# Resolver.net
KiCad netlist of a schematic drawn in Altium Designer
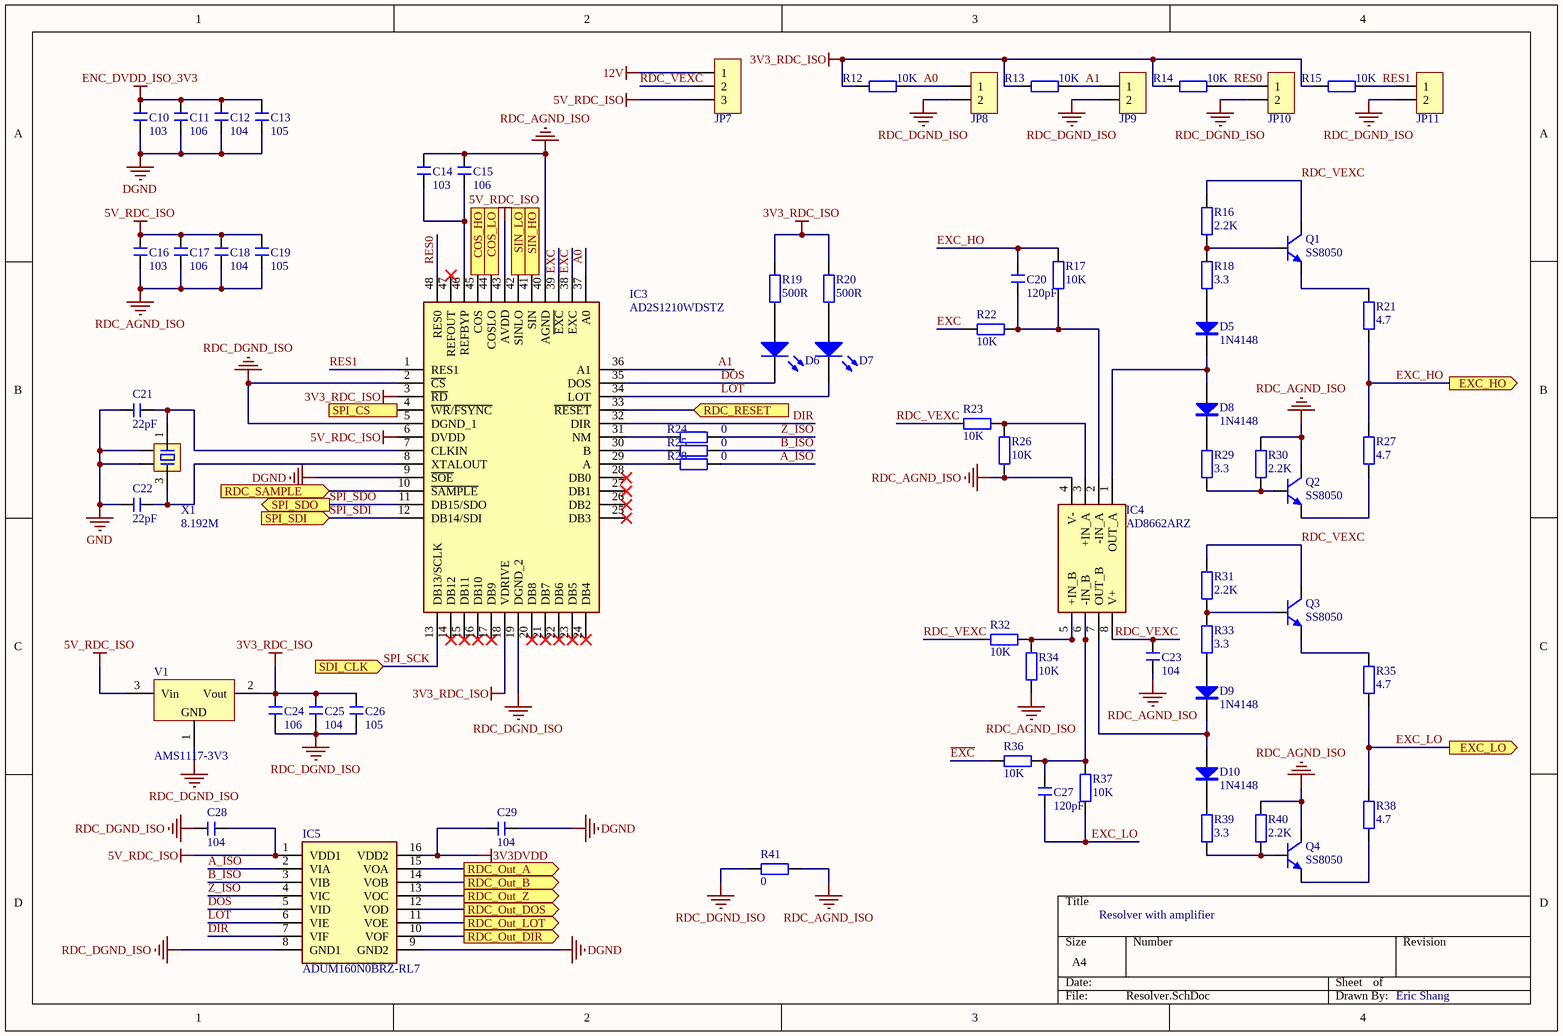
[diagram p0: Resolver.SchDoc]

(export (version "E")
  (design (tool "Eeschema 10.0.6"))
  (components
    (comp (ref "C10")
      (value "103")
      (footprint "C 0603_L")
      (description "贴片电容")
      (libsource (lib "0.1 - 电阻-电容-电感") (part "C"))
    )
    (comp (ref "C11")
      (value "106")
      (footprint "C 0603_L")
      (description "贴片电容")
      (libsource (lib "0.1 - 电阻-电容-电感") (part "C"))
    )
    (comp (ref "C12")
      (value "104")
      (footprint "C 0603_L")
      (description "贴片电容")
      (libsource (lib "0.1 - 电阻-电容-电感") (part "C"))
    )
    (comp (ref "C13")
      (value "105")
      (footprint "C 0603_L")
      (description "贴片电容")
      (libsource (lib "0.1 - 电阻-电容-电感") (part "C"))
    )
    (comp (ref "C14")
      (value "103")
      (footprint "C 0603_L")
      (description "贴片电容")
      (libsource (lib "0.1 - 电阻-电容-电感") (part "C"))
    )
    (comp (ref "C15")
      (value "106")
      (footprint "C 0603_L")
      (description "贴片电容")
      (libsource (lib "0.1 - 电阻-电容-电感") (part "C"))
    )
    (comp (ref "C16")
      (value "103")
      (footprint "C 0603_L")
      (description "贴片电容")
      (libsource (lib "0.1 - 电阻-电容-电感") (part "C"))
    )
    (comp (ref "C17")
      (value "106")
      (footprint "C 0603_L")
      (description "贴片电容")
      (libsource (lib "0.1 - 电阻-电容-电感") (part "C"))
    )
    (comp (ref "C18")
      (value "104")
      (footprint "C 0603_L")
      (description "贴片电容")
      (libsource (lib "0.1 - 电阻-电容-电感") (part "C"))
    )
    (comp (ref "C19")
      (value "105")
      (footprint "C 0603_L")
      (description "贴片电容")
      (libsource (lib "0.1 - 电阻-电容-电感") (part "C"))
    )
    (comp (ref "C20")
      (value "120pF")
      (footprint "C 0603_L")
      (description "贴片电容")
      (libsource (lib "0.1 - 电阻-电容-电感") (part "C"))
    )
    (comp (ref "C21")
      (value "22pF")
      (footprint "C 0603_L")
      (description "贴片电容")
      (libsource (lib "0.1 - 电阻-电容-电感") (part "C"))
    )
    (comp (ref "C22")
      (value "22pF")
      (footprint "C 0603_L")
      (description "贴片电容")
      (libsource (lib "0.1 - 电阻-电容-电感") (part "C"))
    )
    (comp (ref "C23")
      (value "104")
      (footprint "C 0603_L")
      (description "贴片电容")
      (libsource (lib "0.1 - 电阻-电容-电感") (part "C"))
    )
    (comp (ref "C24")
      (value "106")
      (footprint "C 0603_L")
      (description "贴片电容")
      (libsource (lib "0.1 - 电阻-电容-电感") (part "C"))
    )
    (comp (ref "C25")
      (value "104")
      (footprint "C 0603_L")
      (description "贴片电容")
      (libsource (lib "0.1 - 电阻-电容-电感") (part "C"))
    )
    (comp (ref "C26")
      (value "105")
      (footprint "C 0603_L")
      (description "贴片电容")
      (libsource (lib "0.1 - 电阻-电容-电感") (part "C"))
    )
    (comp (ref "C27")
      (value "120pF")
      (footprint "C 0603_L")
      (description "贴片电容")
      (libsource (lib "0.1 - 电阻-电容-电感") (part "C"))
    )
    (comp (ref "C28")
      (value "104")
      (footprint "C 0603_L")
      (description "贴片电容")
      (libsource (lib "0.1 - 电阻-电容-电感") (part "C"))
    )
    (comp (ref "C29")
      (value "104")
      (footprint "C 0603_L")
      (description "贴片电容")
      (libsource (lib "0.1 - 电阻-电容-电感") (part "C"))
    )
    (comp (ref "D5")
      (value "1N4148")
      (footprint "MINI_MELF (LL34)")
      (description "开关二极管")
      (libsource (lib "0.2 -  二极管-整流桥") (part "1N4148"))
    )
    (comp (ref "D6")
      (value "LED")
      (footprint "LED 0603W")
      (description "发光二极管")
      (libsource (lib "0.3 - LED发光二极管") (part "LED"))
    )
    (comp (ref "D7")
      (value "LED")
      (footprint "LED 0603W")
      (description "发光二极管")
      (libsource (lib "0.3 - LED发光二极管") (part "LED"))
    )
    (comp (ref "D8")
      (value "1N4148")
      (footprint "MINI_MELF (LL34)")
      (description "开关二极管")
      (libsource (lib "0.2 -  二极管-整流桥") (part "1N4148"))
    )
    (comp (ref "D9")
      (value "1N4148")
      (footprint "MINI_MELF (LL34)")
      (description "开关二极管")
      (libsource (lib "0.2 -  二极管-整流桥") (part "1N4148"))
    )
    (comp (ref "D10")
      (value "1N4148")
      (footprint "MINI_MELF (LL34)")
      (description "开关二极管")
      (libsource (lib "0.2 -  二极管-整流桥") (part "1N4148"))
    )
    (comp (ref "IC3")
      (value "AD2S1210WDSTZ")
      (footprint "SkylakeADPcbLib:QFP50P900X900X160-48N")
      (description "Integrated Circuit")
      (fields (field (name "MOUSER PART NUMBER") "584-AD2S1210WDSTZ"))
      (libsource (lib "*") (part "AD2S1210WDSTZ"))
    )
    (comp (ref "IC4")
      (value "AD8662ARZ")
      (footprint "SkylakeADPcbLib:SOIC127P600X175-8N")
      (description "Integrated Circuit")
      (fields (field (name "MOUSER PART NUMBER") "584-AD8662ARZ"))
      (libsource (lib "*") (part "AD8662ARZ"))
    )
    (comp (ref "IC5")
      (value "ADUM160N0BRZ-RL7")
      (footprint "SkylakeADPcbLib:SOIC127P600X175-16N")
      (description "Integrated Circuit")
      (fields (field (name "MOUSER PART NUMBER") "584-ADUM160N0BRZ-RL7"))
      (libsource (lib "*") (part "ADUM160N0BRZ-RL7"))
    )
    (comp (ref "JP7")
      (value "HDR-1X3")
      (footprint "HDR2.54-LI-3P")
      (description "3P接插件")
      (fields (field (name "版权归属") "封装库来自淘宝 ID：黄晶宝石"))
      (libsource (lib "5.3 - 接插件-脚距2.54 (100mil) ") (part "Header 3"))
    )
    (comp (ref "JP8")
      (value "HDR-1X2")
      (footprint "HDR2.54-LI-2P")
      (description "2P接插件")
      (fields (field (name "版权归属") "封装库来自淘宝 ID：黄晶宝石"))
      (libsource (lib "5.3 - 接插件-脚距2.54 (100mil) ") (part "Header 2"))
    )
    (comp (ref "JP9")
      (value "HDR-1X2")
      (footprint "HDR2.54-LI-2P")
      (description "2P接插件")
      (fields (field (name "版权归属") "封装库来自淘宝 ID：黄晶宝石"))
      (libsource (lib "5.3 - 接插件-脚距2.54 (100mil) ") (part "Header 2"))
    )
    (comp (ref "JP10")
      (value "HDR-1X2")
      (footprint "HDR2.54-LI-2P")
      (description "2P接插件")
      (fields (field (name "版权归属") "封装库来自淘宝 ID：黄晶宝石"))
      (libsource (lib "5.3 - 接插件-脚距2.54 (100mil) ") (part "Header 2"))
    )
    (comp (ref "JP11")
      (value "HDR-1X2")
      (footprint "HDR2.54-LI-2P")
      (description "2P接插件")
      (fields (field (name "版权归属") "封装库来自淘宝 ID：黄晶宝石"))
      (libsource (lib "5.3 - 接插件-脚距2.54 (100mil) ") (part "Header 2"))
    )
    (comp (ref "Q1")
      (value "SS8050")
      (footprint "SOT23-3N")
      (description "高频放大-NPN型")
      (fields (field (name "版权归属") "封装库来自淘宝 ID：黄晶宝石"))
      (libsource (lib "0.4 - 三极管") (part "8050-SMD"))
    )
    (comp (ref "Q2")
      (value "SS8050")
      (footprint "SOT23-3N")
      (description "高频放大-NPN型")
      (fields (field (name "版权归属") "封装库来自淘宝 ID：黄晶宝石"))
      (libsource (lib "0.4 - 三极管") (part "8050-SMD"))
    )
    (comp (ref "Q3")
      (value "SS8050")
      (footprint "SOT23-3N")
      (description "高频放大-NPN型")
      (fields (field (name "版权归属") "封装库来自淘宝 ID：黄晶宝石"))
      (libsource (lib "0.4 - 三极管") (part "8050-SMD"))
    )
    (comp (ref "Q4")
      (value "SS8050")
      (footprint "SOT23-3N")
      (description "高频放大-NPN型")
      (fields (field (name "版权归属") "封装库来自淘宝 ID：黄晶宝石"))
      (libsource (lib "0.4 - 三极管") (part "8050-SMD"))
    )
    (comp (ref "R12")
      (value "10K")
      (footprint "R 0603_L")
      (description "贴片电阻")
      (fields (field (name "版权归属") "来自淘宝 ID：黄晶宝石"))
      (libsource (lib "0.1 - 电阻-电容-电感") (part "R"))
    )
    (comp (ref "R13")
      (value "10K")
      (footprint "R 0603_L")
      (description "贴片电阻")
      (fields (field (name "版权归属") "来自淘宝 ID：黄晶宝石"))
      (libsource (lib "0.1 - 电阻-电容-电感") (part "R"))
    )
    (comp (ref "R14")
      (value "10K")
      (footprint "R 0603_L")
      (description "贴片电阻")
      (fields (field (name "版权归属") "来自淘宝 ID：黄晶宝石"))
      (libsource (lib "0.1 - 电阻-电容-电感") (part "R"))
    )
    (comp (ref "R15")
      (value "10K")
      (footprint "R 0603_L")
      (description "贴片电阻")
      (fields (field (name "版权归属") "来自淘宝 ID：黄晶宝石"))
      (libsource (lib "0.1 - 电阻-电容-电感") (part "R"))
    )
    (comp (ref "R16")
      (value "2.2K")
      (footprint "R 0603_L")
      (description "贴片电阻")
      (fields (field (name "版权归属") "来自淘宝 ID：黄晶宝石"))
      (libsource (lib "0.1 - 电阻-电容-电感") (part "R"))
    )
    (comp (ref "R17")
      (value "10K")
      (footprint "R 0603_L")
      (description "贴片电阻")
      (fields (field (name "版权归属") "来自淘宝 ID：黄晶宝石"))
      (libsource (lib "0.1 - 电阻-电容-电感") (part "R"))
    )
    (comp (ref "R18")
      (value "3.3")
      (footprint "R 0603_L")
      (description "贴片电阻")
      (fields (field (name "版权归属") "来自淘宝 ID：黄晶宝石"))
      (libsource (lib "0.1 - 电阻-电容-电感") (part "R"))
    )
    (comp (ref "R19")
      (value "500R")
      (footprint "R 0603_L")
      (description "贴片电阻")
      (fields (field (name "版权归属") "来自淘宝 ID：黄晶宝石"))
      (libsource (lib "0.1 - 电阻-电容-电感") (part "R"))
    )
    (comp (ref "R20")
      (value "500R")
      (footprint "R 0603_L")
      (description "贴片电阻")
      (fields (field (name "版权归属") "来自淘宝 ID：黄晶宝石"))
      (libsource (lib "0.1 - 电阻-电容-电感") (part "R"))
    )
    (comp (ref "R21")
      (value "4.7")
      (footprint "R 1206_L")
      (description "贴片电阻")
      (fields (field (name "版权归属") "来自淘宝 ID：黄晶宝石"))
      (libsource (lib "0.1 - 电阻-电容-电感") (part "R"))
    )
    (comp (ref "R22")
      (value "10K")
      (footprint "R 0603_L")
      (description "贴片电阻")
      (fields (field (name "版权归属") "来自淘宝 ID：黄晶宝石"))
      (libsource (lib "0.1 - 电阻-电容-电感") (part "R"))
    )
    (comp (ref "R23")
      (value "10K")
      (footprint "R 0603_L")
      (description "贴片电阻")
      (fields (field (name "版权归属") "来自淘宝 ID：黄晶宝石"))
      (libsource (lib "0.1 - 电阻-电容-电感") (part "R"))
    )
    (comp (ref "R24")
      (value "0")
      (footprint "R 0603_L")
      (description "贴片电阻")
      (fields (field (name "版权归属") "来自淘宝 ID：黄晶宝石"))
      (libsource (lib "0.1 - 电阻-电容-电感") (part "R"))
    )
    (comp (ref "R25")
      (value "0")
      (footprint "R 0603_L")
      (description "贴片电阻")
      (fields (field (name "版权归属") "来自淘宝 ID：黄晶宝石"))
      (libsource (lib "0.1 - 电阻-电容-电感") (part "R"))
    )
    (comp (ref "R26")
      (value "10K")
      (footprint "R 0603_L")
      (description "贴片电阻")
      (fields (field (name "版权归属") "来自淘宝 ID：黄晶宝石"))
      (libsource (lib "0.1 - 电阻-电容-电感") (part "R"))
    )
    (comp (ref "R27")
      (value "4.7")
      (footprint "R 1206_L")
      (description "贴片电阻")
      (fields (field (name "版权归属") "来自淘宝 ID：黄晶宝石"))
      (libsource (lib "0.1 - 电阻-电容-电感") (part "R"))
    )
    (comp (ref "R28")
      (value "0")
      (footprint "R 0603_L")
      (description "贴片电阻")
      (fields (field (name "版权归属") "来自淘宝 ID：黄晶宝石"))
      (libsource (lib "0.1 - 电阻-电容-电感") (part "R"))
    )
    (comp (ref "R29")
      (value "3.3")
      (footprint "R 0603_L")
      (description "贴片电阻")
      (fields (field (name "版权归属") "来自淘宝 ID：黄晶宝石"))
      (libsource (lib "0.1 - 电阻-电容-电感") (part "R"))
    )
    (comp (ref "R30")
      (value "2.2K")
      (footprint "R 0603_L")
      (description "贴片电阻")
      (fields (field (name "版权归属") "来自淘宝 ID：黄晶宝石"))
      (libsource (lib "0.1 - 电阻-电容-电感") (part "R"))
    )
    (comp (ref "R31")
      (value "2.2K")
      (footprint "R 0603_L")
      (description "贴片电阻")
      (fields (field (name "版权归属") "来自淘宝 ID：黄晶宝石"))
      (libsource (lib "0.1 - 电阻-电容-电感") (part "R"))
    )
    (comp (ref "R32")
      (value "10K")
      (footprint "R 0603_L")
      (description "贴片电阻")
      (fields (field (name "版权归属") "来自淘宝 ID：黄晶宝石"))
      (libsource (lib "0.1 - 电阻-电容-电感") (part "R"))
    )
    (comp (ref "R33")
      (value "3.3")
      (footprint "R 0603_L")
      (description "贴片电阻")
      (fields (field (name "版权归属") "来自淘宝 ID：黄晶宝石"))
      (libsource (lib "0.1 - 电阻-电容-电感") (part "R"))
    )
    (comp (ref "R34")
      (value "10K")
      (footprint "R 0603_L")
      (description "贴片电阻")
      (fields (field (name "版权归属") "来自淘宝 ID：黄晶宝石"))
      (libsource (lib "0.1 - 电阻-电容-电感") (part "R"))
    )
    (comp (ref "R35")
      (value "4.7")
      (footprint "R 1206_L")
      (description "贴片电阻")
      (fields (field (name "版权归属") "来自淘宝 ID：黄晶宝石"))
      (libsource (lib "0.1 - 电阻-电容-电感") (part "R"))
    )
    (comp (ref "R36")
      (value "10K")
      (footprint "R 0603_L")
      (description "贴片电阻")
      (fields (field (name "版权归属") "来自淘宝 ID：黄晶宝石"))
      (libsource (lib "0.1 - 电阻-电容-电感") (part "R"))
    )
    (comp (ref "R37")
      (value "10K")
      (footprint "R 0603_L")
      (description "贴片电阻")
      (fields (field (name "版权归属") "来自淘宝 ID：黄晶宝石"))
      (libsource (lib "0.1 - 电阻-电容-电感") (part "R"))
    )
    (comp (ref "R38")
      (value "4.7")
      (footprint "R 1206_L")
      (description "贴片电阻")
      (fields (field (name "版权归属") "来自淘宝 ID：黄晶宝石"))
      (libsource (lib "0.1 - 电阻-电容-电感") (part "R"))
    )
    (comp (ref "R39")
      (value "3.3")
      (footprint "R 0603_L")
      (description "贴片电阻")
      (fields (field (name "版权归属") "来自淘宝 ID：黄晶宝石"))
      (libsource (lib "0.1 - 电阻-电容-电感") (part "R"))
    )
    (comp (ref "R40")
      (value "2.2K")
      (footprint "R 0603_L")
      (description "贴片电阻")
      (fields (field (name "版权归属") "来自淘宝 ID：黄晶宝石"))
      (libsource (lib "0.1 - 电阻-电容-电感") (part "R"))
    )
    (comp (ref "R41")
      (value "0")
      (footprint "R 1206_L")
      (description "贴片电阻")
      (fields (field (name "版权归属") "来自淘宝 ID：黄晶宝石"))
      (libsource (lib "0.1 - 电阻-电容-电感") (part "R"))
    )
    (comp (ref "V1")
      (value "AMS1117-3V3")
      (footprint "SOT223_L")
      (description "三端稳压芯片")
      (libsource (lib "1.1 - 电源类芯片") (part "AMS1117"))
    )
    (comp (ref "X1")
      (value "8.192M")
      (footprint "OSC 1612-4P")
      (description "4脚无源晶振")
      (fields (field (name "版权归属") "封装库来自淘宝卖家 ID：黄晶宝石"))
      (libsource (lib "2.0 - 保险丝-晶振-光耦") (part "XTAL-4P"))
    )
  )
  (nets
    (net (code "1") (name "/A0") (class "Default")
      (node (ref "IC3") (pin "37") (pinfunction "A0_37") (pintype "passive"))
      (node (ref "JP8") (pin "1") (pinfunction "1_1") (pintype "passive"))
      (node (ref "R12") (pin "2") (pinfunction "2_2") (pintype "passive"))
    )
    (net (code "2") (name "/A1") (class "Default")
      (node (ref "IC3") (pin "36") (pinfunction "A1_36") (pintype "passive"))
      (node (ref "JP9") (pin "1") (pinfunction "1_1") (pintype "passive"))
      (node (ref "R13") (pin "2") (pinfunction "2_2") (pintype "passive"))
    )
    (net (code "3") (name "/A_ISO") (class "Default")
      (node (ref "IC5") (pin "2") (pinfunction "VIA_2") (pintype "passive"))
      (node (ref "R28") (pin "2") (pinfunction "2_2") (pintype "passive"))
    )
    (net (code "4") (name "/B_ISO") (class "Default")
      (node (ref "IC5") (pin "3") (pinfunction "VIB_3") (pintype "passive"))
      (node (ref "R25") (pin "2") (pinfunction "2_2") (pintype "passive"))
    )
    (net (code "5") (name "/COS_HO") (class "Default")
      (node (ref "IC3") (pin "45") (pinfunction "COS_45") (pintype "passive"))
    )
    (net (code "6") (name "/COS_LO") (class "Default")
      (node (ref "IC3") (pin "44") (pinfunction "COSLO_44") (pintype "passive"))
    )
    (net (code "7") (name "/DIR") (class "Default")
      (node (ref "IC3") (pin "32") (pinfunction "DIR_32") (pintype "passive"))
      (node (ref "IC5") (pin "7") (pinfunction "VIF_7") (pintype "passive"))
    )
    (net (code "8") (name "/DOS") (class "Default")
      (node (ref "D6") (pin "2") (pinfunction "K_2") (pintype "passive"))
      (node (ref "IC3") (pin "35") (pinfunction "DOS_35") (pintype "passive"))
      (node (ref "IC5") (pin "5") (pinfunction "VID_5") (pintype "passive"))
    )
    (net (code "9") (name "/EXC") (class "Default")
      (node (ref "IC3") (pin "38") (pinfunction "EXC_38") (pintype "passive"))
      (node (ref "R22") (pin "1") (pinfunction "1_1") (pintype "passive"))
    )
    (net (code "10") (name "/EXC_HO") (class "Default")
      (node (ref "C20") (pin "2") (pinfunction "2_2") (pintype "passive"))
      (node (ref "R17") (pin "2") (pinfunction "2_2") (pintype "passive"))
      (node (ref "R21") (pin "1") (pinfunction "1_1") (pintype "passive"))
      (node (ref "R27") (pin "2") (pinfunction "2_2") (pintype "passive"))
    )
    (net (code "11") (name "/EXC_LO") (class "Default")
      (node (ref "C27") (pin "1") (pinfunction "1_1") (pintype "passive"))
      (node (ref "R35") (pin "1") (pinfunction "1_1") (pintype "passive"))
      (node (ref "R37") (pin "1") (pinfunction "1_1") (pintype "passive"))
      (node (ref "R38") (pin "2") (pinfunction "2_2") (pintype "passive"))
    )
    (net (code "12") (name "/LOT") (class "Default")
      (node (ref "D7") (pin "2") (pinfunction "K_2") (pintype "passive"))
      (node (ref "IC3") (pin "34") (pinfunction "LOT_34") (pintype "passive"))
      (node (ref "IC5") (pin "6") (pinfunction "VIE_6") (pintype "passive"))
    )
    (net (code "13") (name "/RDC_Out_A") (class "Default")
      (node (ref "IC5") (pin "15") (pinfunction "VOA_15") (pintype "passive"))
    )
    (net (code "14") (name "/RDC_Out_B") (class "Default")
      (node (ref "IC5") (pin "14") (pinfunction "VOB_14") (pintype "passive"))
    )
    (net (code "15") (name "/RDC_Out_DIR") (class "Default")
      (node (ref "IC5") (pin "10") (pinfunction "VOF_10") (pintype "passive"))
    )
    (net (code "16") (name "/RDC_Out_DOS") (class "Default")
      (node (ref "IC5") (pin "12") (pinfunction "VOD_12") (pintype "passive"))
    )
    (net (code "17") (name "/RDC_Out_LOT") (class "Default")
      (node (ref "IC5") (pin "11") (pinfunction "VOE_11") (pintype "passive"))
    )
    (net (code "18") (name "/RDC_Out_Z") (class "Default")
      (node (ref "IC5") (pin "13") (pinfunction "VOC_13") (pintype "passive"))
    )
    (net (code "19") (name "/RDC_RESET") (class "Default")
      (node (ref "IC3") (pin "33") (pinfunction "~{RESET}_33") (pintype "passive"))
    )
    (net (code "20") (name "/RDC_SAMPLE") (class "Default")
      (node (ref "IC3") (pin "10") (pinfunction "~{SAMPLE}_10") (pintype "passive"))
    )
    (net (code "21") (name "/RDC_VEXC") (class "Default")
      (node (ref "C23") (pin "2") (pinfunction "2_2") (pintype "passive"))
      (node (ref "IC4") (pin "8") (pinfunction "V+_8") (pintype "passive"))
      (node (ref "JP7") (pin "2") (pinfunction "2_2") (pintype "passive"))
      (node (ref "Q1") (pin "3") (pinfunction "C_3") (pintype "passive"))
      (node (ref "Q3") (pin "3") (pinfunction "C_3") (pintype "passive"))
      (node (ref "R16") (pin "2") (pinfunction "2_2") (pintype "passive"))
      (node (ref "R23") (pin "1") (pinfunction "1_1") (pintype "passive"))
      (node (ref "R31") (pin "2") (pinfunction "2_2") (pintype "passive"))
      (node (ref "R32") (pin "1") (pinfunction "1_1") (pintype "passive"))
    )
    (net (code "22") (name "/RES0") (class "Default")
      (node (ref "IC3") (pin "48") (pinfunction "RES0_48") (pintype "passive"))
      (node (ref "JP10") (pin "1") (pinfunction "1_1") (pintype "passive"))
      (node (ref "R14") (pin "2") (pinfunction "2_2") (pintype "passive"))
    )
    (net (code "23") (name "/RES1") (class "Default")
      (node (ref "IC3") (pin "1") (pinfunction "RES1_1") (pintype "passive"))
      (node (ref "JP11") (pin "1") (pinfunction "1_1") (pintype "passive"))
      (node (ref "R15") (pin "2") (pinfunction "2_2") (pintype "passive"))
    )
    (net (code "24") (name "/SIN_HO") (class "Default")
      (node (ref "IC3") (pin "41") (pinfunction "SIN_41") (pintype "passive"))
    )
    (net (code "25") (name "/SIN_LO") (class "Default")
      (node (ref "IC3") (pin "42") (pinfunction "SINLO_42") (pintype "passive"))
    )
    (net (code "26") (name "/SPI_CS") (class "Default")
      (node (ref "IC3") (pin "4") (pinfunction "~{WR}/~{FSYNC}_4") (pintype "passive"))
    )
    (net (code "27") (name "/SPI_SCK") (class "Default")
      (node (ref "IC3") (pin "13") (pinfunction "DB13/SCLK_13") (pintype "passive"))
    )
    (net (code "28") (name "/SPI_SDI") (class "Default")
      (node (ref "IC3") (pin "12") (pinfunction "DB14/SDI_12") (pintype "passive"))
    )
    (net (code "29") (name "/SPI_SDO") (class "Default")
      (node (ref "IC3") (pin "11") (pinfunction "DB15/SDO_11") (pintype "passive"))
    )
    (net (code "30") (name "/Z_ISO") (class "Default")
      (node (ref "IC5") (pin "4") (pinfunction "VIC_4") (pintype "passive"))
      (node (ref "R24") (pin "2") (pinfunction "2_2") (pintype "passive"))
    )
    (net (code "31") (name "/~{EXC}") (class "Default")
      (node (ref "IC3") (pin "39") (pinfunction "~{EXC}_39") (pintype "passive"))
      (node (ref "R36") (pin "1") (pinfunction "1_1") (pintype "passive"))
    )
    (net (code "32") (name "3V3DVDD") (class "Default")
      (node (ref "C29") (pin "1") (pinfunction "1_1") (pintype "passive"))
      (node (ref "IC5") (pin "16") (pinfunction "VDD2_16") (pintype "passive"))
    )
    (net (code "33") (name "3V3_RDC_ISO") (class "Default")
      (node (ref "C24") (pin "2") (pinfunction "2_2") (pintype "passive"))
      (node (ref "C25") (pin "2") (pinfunction "2_2") (pintype "passive"))
      (node (ref "C26") (pin "2") (pinfunction "2_2") (pintype "passive"))
      (node (ref "IC3") (pin "18") (pinfunction "VDRIVE_18") (pintype "passive"))
      (node (ref "IC3") (pin "3") (pinfunction "~{RD}_3") (pintype "passive"))
      (node (ref "R12") (pin "1") (pinfunction "1_1") (pintype "passive"))
      (node (ref "R13") (pin "1") (pinfunction "1_1") (pintype "passive"))
      (node (ref "R14") (pin "1") (pinfunction "1_1") (pintype "passive"))
      (node (ref "R15") (pin "1") (pinfunction "1_1") (pintype "passive"))
      (node (ref "R19") (pin "2") (pinfunction "2_2") (pintype "passive"))
      (node (ref "R20") (pin "2") (pinfunction "2_2") (pintype "passive"))
      (node (ref "V1") (pin "2") (pinfunction "Vout_2") (pintype "passive"))
    )
    (net (code "34") (name "5V_RDC_ISO") (class "Default")
      (node (ref "C16") (pin "2") (pinfunction "2_2") (pintype "passive"))
      (node (ref "C17") (pin "2") (pinfunction "2_2") (pintype "passive"))
      (node (ref "C18") (pin "2") (pinfunction "2_2") (pintype "passive"))
      (node (ref "C19") (pin "2") (pinfunction "2_2") (pintype "passive"))
      (node (ref "C28") (pin "1") (pinfunction "1_1") (pintype "passive"))
      (node (ref "IC3") (pin "43") (pinfunction "AVDD_43") (pintype "passive"))
      (node (ref "IC3") (pin "6") (pinfunction "DVDD_6") (pintype "passive"))
      (node (ref "IC5") (pin "1") (pinfunction "VDD1_1") (pintype "passive"))
      (node (ref "JP7") (pin "3") (pinfunction "3_3") (pintype "passive"))
      (node (ref "V1") (pin "3") (pinfunction "Vin_3") (pintype "passive"))
    )
    (net (code "35") (name "12V") (class "Default")
      (node (ref "JP7") (pin "1") (pinfunction "1_1") (pintype "passive"))
    )
    (net (code "36") (name "DGND") (class "Default")
      (node (ref "C10") (pin "1") (pinfunction "1_1") (pintype "passive"))
      (node (ref "C11") (pin "1") (pinfunction "1_1") (pintype "passive"))
      (node (ref "C12") (pin "1") (pinfunction "1_1") (pintype "passive"))
      (node (ref "C13") (pin "1") (pinfunction "1_1") (pintype "passive"))
      (node (ref "C29") (pin "2") (pinfunction "2_2") (pintype "passive"))
      (node (ref "IC3") (pin "9") (pinfunction "~{SOE}_9") (pintype "passive"))
      (node (ref "IC5") (pin "9") (pinfunction "GND2_9") (pintype "passive"))
    )
    (net (code "37") (name "ENC_DVDD_ISO_3V3") (class "Default")
      (node (ref "C10") (pin "2") (pinfunction "2_2") (pintype "passive"))
      (node (ref "C11") (pin "2") (pinfunction "2_2") (pintype "passive"))
      (node (ref "C12") (pin "2") (pinfunction "2_2") (pintype "passive"))
      (node (ref "C13") (pin "2") (pinfunction "2_2") (pintype "passive"))
    )
    (net (code "38") (name "GND") (class "Default")
      (node (ref "C21") (pin "1") (pinfunction "1_1") (pintype "passive"))
      (node (ref "C22") (pin "1") (pinfunction "1_1") (pintype "passive"))
      (node (ref "X1") (pin "2") (pinfunction "2_2") (pintype "passive"))
      (node (ref "X1") (pin "4") (pinfunction "4_4") (pintype "passive"))
    )
    (net (code "39") (name "Net-(D5-A)") (class "Default")
      (node (ref "D5") (pin "1") (pinfunction "A_1") (pintype "passive"))
      (node (ref "R18") (pin "1") (pinfunction "1_1") (pintype "passive"))
    )
    (net (code "40") (name "Net-(D5-K)") (class "Default")
      (node (ref "D5") (pin "2") (pinfunction "K_2") (pintype "passive"))
      (node (ref "D8") (pin "1") (pinfunction "A_1") (pintype "passive"))
      (node (ref "IC4") (pin "1") (pinfunction "OUT_A_1") (pintype "passive"))
    )
    (net (code "41") (name "Net-(D6-A)") (class "Default")
      (node (ref "D6") (pin "1") (pinfunction "A_1") (pintype "passive"))
      (node (ref "R19") (pin "1") (pinfunction "1_1") (pintype "passive"))
    )
    (net (code "42") (name "Net-(D7-A)") (class "Default")
      (node (ref "D7") (pin "1") (pinfunction "A_1") (pintype "passive"))
      (node (ref "R20") (pin "1") (pinfunction "1_1") (pintype "passive"))
    )
    (net (code "43") (name "Net-(D8-K)") (class "Default")
      (node (ref "D8") (pin "2") (pinfunction "K_2") (pintype "passive"))
      (node (ref "R29") (pin "2") (pinfunction "2_2") (pintype "passive"))
    )
    (net (code "44") (name "Net-(D9-A)") (class "Default")
      (node (ref "D9") (pin "1") (pinfunction "A_1") (pintype "passive"))
      (node (ref "R33") (pin "1") (pinfunction "1_1") (pintype "passive"))
    )
    (net (code "45") (name "Net-(D10-A)") (class "Default")
      (node (ref "D10") (pin "1") (pinfunction "A_1") (pintype "passive"))
      (node (ref "D9") (pin "2") (pinfunction "K_2") (pintype "passive"))
      (node (ref "IC4") (pin "7") (pinfunction "OUT_B_7") (pintype "passive"))
    )
    (net (code "46") (name "Net-(D10-K)") (class "Default")
      (node (ref "D10") (pin "2") (pinfunction "K_2") (pintype "passive"))
      (node (ref "R39") (pin "2") (pinfunction "2_2") (pintype "passive"))
    )
    (net (code "47") (name "Net-(IC3-A)") (class "Default")
      (node (ref "IC3") (pin "29") (pinfunction "A_29") (pintype "passive"))
      (node (ref "R28") (pin "1") (pinfunction "1_1") (pintype "passive"))
    )
    (net (code "48") (name "Net-(IC3-B)") (class "Default")
      (node (ref "IC3") (pin "30") (pinfunction "B_30") (pintype "passive"))
      (node (ref "R25") (pin "1") (pinfunction "1_1") (pintype "passive"))
    )
    (net (code "49") (name "Net-(IC3-CLKIN)") (class "Default")
      (node (ref "C21") (pin "2") (pinfunction "2_2") (pintype "passive"))
      (node (ref "IC3") (pin "7") (pinfunction "CLKIN_7") (pintype "passive"))
      (node (ref "X1") (pin "1") (pinfunction "1_1") (pintype "passive"))
    )
    (net (code "50") (name "Net-(IC3-NM)") (class "Default")
      (node (ref "IC3") (pin "31") (pinfunction "NM_31") (pintype "passive"))
      (node (ref "R24") (pin "1") (pinfunction "1_1") (pintype "passive"))
    )
    (net (code "51") (name "Net-(IC3-REFBYP)") (class "Default")
      (node (ref "C14") (pin "1") (pinfunction "1_1") (pintype "passive"))
      (node (ref "C15") (pin "1") (pinfunction "1_1") (pintype "passive"))
      (node (ref "IC3") (pin "46") (pinfunction "REFBYP_46") (pintype "passive"))
    )
    (net (code "52") (name "Net-(IC3-XTALOUT)") (class "Default")
      (node (ref "C22") (pin "2") (pinfunction "2_2") (pintype "passive"))
      (node (ref "IC3") (pin "8") (pinfunction "XTALOUT_8") (pintype "passive"))
      (node (ref "X1") (pin "3") (pinfunction "3_3") (pintype "passive"))
    )
    (net (code "53") (name "Net-(IC4-+IN_A)") (class "Default")
      (node (ref "IC4") (pin "3") (pinfunction "+IN_A_3") (pintype "passive"))
      (node (ref "R23") (pin "2") (pinfunction "2_2") (pintype "passive"))
      (node (ref "R26") (pin "2") (pinfunction "2_2") (pintype "passive"))
    )
    (net (code "54") (name "Net-(IC4-+IN_B)") (class "Default")
      (node (ref "IC4") (pin "5") (pinfunction "+IN_B_5") (pintype "passive"))
      (node (ref "R32") (pin "2") (pinfunction "2_2") (pintype "passive"))
      (node (ref "R34") (pin "2") (pinfunction "2_2") (pintype "passive"))
    )
    (net (code "55") (name "Net-(IC4--IN_A)") (class "Default")
      (node (ref "C20") (pin "1") (pinfunction "1_1") (pintype "passive"))
      (node (ref "IC4") (pin "2") (pinfunction "-IN_A_2") (pintype "passive"))
      (node (ref "R17") (pin "1") (pinfunction "1_1") (pintype "passive"))
      (node (ref "R22") (pin "2") (pinfunction "2_2") (pintype "passive"))
    )
    (net (code "56") (name "Net-(IC4--IN_B)") (class "Default")
      (node (ref "C27") (pin "2") (pinfunction "2_2") (pintype "passive"))
      (node (ref "IC4") (pin "6") (pinfunction "-IN_B_6") (pintype "passive"))
      (node (ref "R36") (pin "2") (pinfunction "2_2") (pintype "passive"))
      (node (ref "R37") (pin "2") (pinfunction "2_2") (pintype "passive"))
    )
    (net (code "57") (name "Net-(Q1-B)") (class "Default")
      (node (ref "Q1") (pin "1") (pinfunction "B_1") (pintype "passive"))
      (node (ref "R16") (pin "1") (pinfunction "1_1") (pintype "passive"))
      (node (ref "R18") (pin "2") (pinfunction "2_2") (pintype "passive"))
    )
    (net (code "58") (name "Net-(Q1-E)") (class "Default")
      (node (ref "Q1") (pin "2") (pinfunction "E_2") (pintype "passive"))
      (node (ref "R21") (pin "2") (pinfunction "2_2") (pintype "passive"))
    )
    (net (code "59") (name "Net-(Q2-B)") (class "Default")
      (node (ref "Q2") (pin "1") (pinfunction "B_1") (pintype "passive"))
      (node (ref "R29") (pin "1") (pinfunction "1_1") (pintype "passive"))
      (node (ref "R30") (pin "1") (pinfunction "1_1") (pintype "passive"))
    )
    (net (code "60") (name "Net-(Q2-E)") (class "Default")
      (node (ref "Q2") (pin "2") (pinfunction "E_2") (pintype "passive"))
      (node (ref "R27") (pin "1") (pinfunction "1_1") (pintype "passive"))
    )
    (net (code "61") (name "Net-(Q3-B)") (class "Default")
      (node (ref "Q3") (pin "1") (pinfunction "B_1") (pintype "passive"))
      (node (ref "R31") (pin "1") (pinfunction "1_1") (pintype "passive"))
      (node (ref "R33") (pin "2") (pinfunction "2_2") (pintype "passive"))
    )
    (net (code "62") (name "Net-(Q3-E)") (class "Default")
      (node (ref "Q3") (pin "2") (pinfunction "E_2") (pintype "passive"))
      (node (ref "R35") (pin "2") (pinfunction "2_2") (pintype "passive"))
    )
    (net (code "63") (name "Net-(Q4-B)") (class "Default")
      (node (ref "Q4") (pin "1") (pinfunction "B_1") (pintype "passive"))
      (node (ref "R39") (pin "1") (pinfunction "1_1") (pintype "passive"))
      (node (ref "R40") (pin "1") (pinfunction "1_1") (pintype "passive"))
    )
    (net (code "64") (name "Net-(Q4-E)") (class "Default")
      (node (ref "Q4") (pin "2") (pinfunction "E_2") (pintype "passive"))
      (node (ref "R38") (pin "1") (pinfunction "1_1") (pintype "passive"))
    )
    (net (code "65") (name "RDC_AGND_ISO") (class "Default")
      (node (ref "C14") (pin "2") (pinfunction "2_2") (pintype "passive"))
      (node (ref "C15") (pin "2") (pinfunction "2_2") (pintype "passive"))
      (node (ref "C16") (pin "1") (pinfunction "1_1") (pintype "passive"))
      (node (ref "C17") (pin "1") (pinfunction "1_1") (pintype "passive"))
      (node (ref "C18") (pin "1") (pinfunction "1_1") (pintype "passive"))
      (node (ref "C19") (pin "1") (pinfunction "1_1") (pintype "passive"))
      (node (ref "C23") (pin "1") (pinfunction "1_1") (pintype "passive"))
      (node (ref "IC3") (pin "40") (pinfunction "AGND_40") (pintype "passive"))
      (node (ref "IC4") (pin "4") (pinfunction "V-_4") (pintype "passive"))
      (node (ref "Q2") (pin "3") (pinfunction "C_3") (pintype "passive"))
      (node (ref "Q4") (pin "3") (pinfunction "C_3") (pintype "passive"))
      (node (ref "R26") (pin "1") (pinfunction "1_1") (pintype "passive"))
      (node (ref "R30") (pin "2") (pinfunction "2_2") (pintype "passive"))
      (node (ref "R34") (pin "1") (pinfunction "1_1") (pintype "passive"))
      (node (ref "R40") (pin "2") (pinfunction "2_2") (pintype "passive"))
      (node (ref "R41") (pin "1") (pinfunction "1_1") (pintype "passive"))
    )
    (net (code "66") (name "RDC_DGND_ISO") (class "Default")
      (node (ref "C24") (pin "1") (pinfunction "1_1") (pintype "passive"))
      (node (ref "C25") (pin "1") (pinfunction "1_1") (pintype "passive"))
      (node (ref "C26") (pin "1") (pinfunction "1_1") (pintype "passive"))
      (node (ref "C28") (pin "2") (pinfunction "2_2") (pintype "passive"))
      (node (ref "IC3") (pin "19") (pinfunction "DGND_2_19") (pintype "passive"))
      (node (ref "IC3") (pin "2") (pinfunction "~{CS}_2") (pintype "passive"))
      (node (ref "IC3") (pin "5") (pinfunction "DGND_1_5") (pintype "passive"))
      (node (ref "IC5") (pin "8") (pinfunction "GND1_8") (pintype "passive"))
      (node (ref "JP10") (pin "2") (pinfunction "2_2") (pintype "passive"))
      (node (ref "JP11") (pin "2") (pinfunction "2_2") (pintype "passive"))
      (node (ref "JP8") (pin "2") (pinfunction "2_2") (pintype "passive"))
      (node (ref "JP9") (pin "2") (pinfunction "2_2") (pintype "passive"))
      (node (ref "R41") (pin "2") (pinfunction "2_2") (pintype "passive"))
      (node (ref "V1") (pin "1") (pinfunction "GND_1") (pintype "passive"))
    )
    (net (code "67") (name "unconnected-(IC3-DB0-Pad28)") (class "Default")
      (node (ref "IC3") (pin "28") (pinfunction "DB0_28") (pintype "passive+no_connect"))
    )
    (net (code "68") (name "unconnected-(IC3-DB1-Pad27)") (class "Default")
      (node (ref "IC3") (pin "27") (pinfunction "DB1_27") (pintype "passive+no_connect"))
    )
    (net (code "69") (name "unconnected-(IC3-DB2-Pad26)") (class "Default")
      (node (ref "IC3") (pin "26") (pinfunction "DB2_26") (pintype "passive+no_connect"))
    )
    (net (code "70") (name "unconnected-(IC3-DB3-Pad25)") (class "Default")
      (node (ref "IC3") (pin "25") (pinfunction "DB3_25") (pintype "passive+no_connect"))
    )
    (net (code "71") (name "unconnected-(IC3-DB4-Pad24)") (class "Default")
      (node (ref "IC3") (pin "24") (pinfunction "DB4_24") (pintype "passive+no_connect"))
    )
    (net (code "72") (name "unconnected-(IC3-DB5-Pad23)") (class "Default")
      (node (ref "IC3") (pin "23") (pinfunction "DB5_23") (pintype "passive+no_connect"))
    )
    (net (code "73") (name "unconnected-(IC3-DB6-Pad22)") (class "Default")
      (node (ref "IC3") (pin "22") (pinfunction "DB6_22") (pintype "passive+no_connect"))
    )
    (net (code "74") (name "unconnected-(IC3-DB7-Pad21)") (class "Default")
      (node (ref "IC3") (pin "21") (pinfunction "DB7_21") (pintype "passive+no_connect"))
    )
    (net (code "75") (name "unconnected-(IC3-DB8-Pad20)") (class "Default")
      (node (ref "IC3") (pin "20") (pinfunction "DB8_20") (pintype "passive+no_connect"))
    )
    (net (code "76") (name "unconnected-(IC3-DB9-Pad17)") (class "Default")
      (node (ref "IC3") (pin "17") (pinfunction "DB9_17") (pintype "passive+no_connect"))
    )
    (net (code "77") (name "unconnected-(IC3-DB10-Pad16)") (class "Default")
      (node (ref "IC3") (pin "16") (pinfunction "DB10_16") (pintype "passive+no_connect"))
    )
    (net (code "78") (name "unconnected-(IC3-DB11-Pad15)") (class "Default")
      (node (ref "IC3") (pin "15") (pinfunction "DB11_15") (pintype "passive+no_connect"))
    )
    (net (code "79") (name "unconnected-(IC3-DB12-Pad14)") (class "Default")
      (node (ref "IC3") (pin "14") (pinfunction "DB12_14") (pintype "passive+no_connect"))
    )
    (net (code "80") (name "unconnected-(IC3-REFOUT-Pad47)") (class "Default")
      (node (ref "IC3") (pin "47") (pinfunction "REFOUT_47") (pintype "passive+no_connect"))
    )
  )
)
